# IO_Top_Board.net
KiCad netlist of a schematic drawn in EAGLE
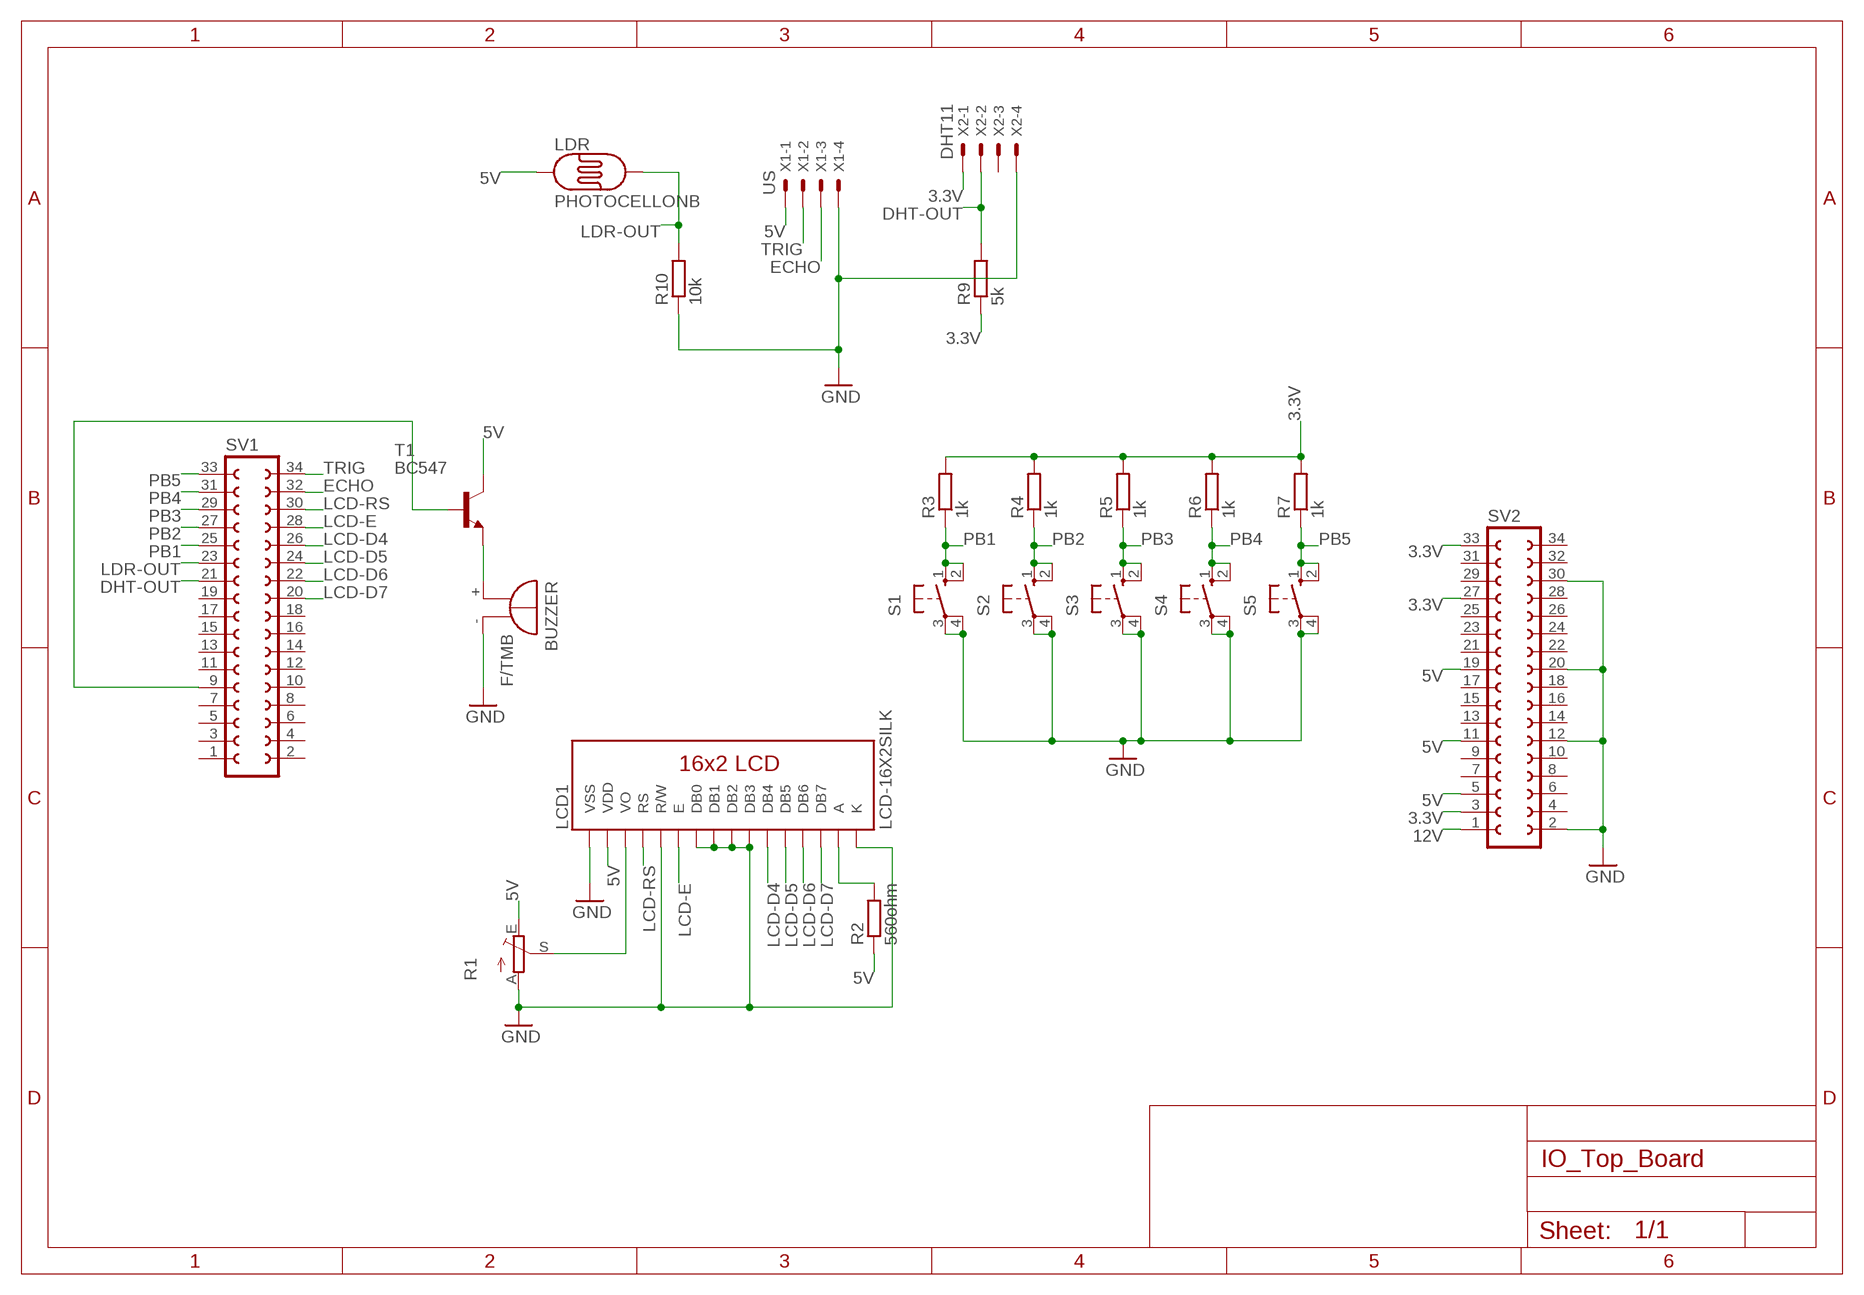
[diagram p0: schematic, sheet 1]

(export (version "E")
  (design (tool "Eeschema 10.0.6"))
  (components
    (comp (ref "BUZZER")
      (value "F/TMB")
      (footprint "eagle-import:F_TMB")
      (libsource (lib "eagle-import") (part "F/TMB"))
    )
    (comp (ref "LCD1")
      (value "LCD-16X2SILK")
      (footprint "eagle-import:LCD-16X2")
      (libsource (lib "eagle-import") (part "LCD-16X2SILK"))
    )
    (comp (ref "LDR")
      (value "PHOTOCELLONB")
      (footprint "eagle-import:ON_BOARD")
      (libsource (lib "eagle-import") (part "PHOTOCELLONB"))
    )
    (comp (ref "R1")
      (value "TRIM_EU-CA6V")
      (footprint "eagle-import:CA6V")
      (libsource (lib "eagle-import") (part "TRIM_EU-CA6V"))
    )
    (comp (ref "R2")
      (value "560ohm")
      (footprint "eagle-import:M0805")
      (libsource (lib "eagle-import") (part "R-EU_M0805"))
    )
    (comp (ref "R3")
      (value "1k")
      (footprint "eagle-import:M0805")
      (libsource (lib "eagle-import") (part "R-EU_M0805"))
    )
    (comp (ref "R4")
      (value "1k")
      (footprint "eagle-import:M0805")
      (libsource (lib "eagle-import") (part "R-EU_M0805"))
    )
    (comp (ref "R5")
      (value "1k")
      (footprint "eagle-import:M0805")
      (libsource (lib "eagle-import") (part "R-EU_M0805"))
    )
    (comp (ref "R6")
      (value "1k")
      (footprint "eagle-import:M0805")
      (libsource (lib "eagle-import") (part "R-EU_M0805"))
    )
    (comp (ref "R7")
      (value "1k")
      (footprint "eagle-import:M0805")
      (libsource (lib "eagle-import") (part "R-EU_M0805"))
    )
    (comp (ref "R9")
      (value "5k")
      (footprint "eagle-import:M0805")
      (libsource (lib "eagle-import") (part "R-EU_M0805"))
    )
    (comp (ref "R10")
      (value "10k")
      (footprint "eagle-import:M0805")
      (libsource (lib "eagle-import") (part "R-EU_M0805"))
    )
    (comp (ref "S1")
      (value "10-XX")
      (footprint "eagle-import:B3F-10XX")
      (fields (field (name "MPN") "B3F-1000"))
      (libsource (lib "eagle-import") (part "10-XX"))
    )
    (comp (ref "S2")
      (value "10-XX")
      (footprint "eagle-import:B3F-10XX")
      (fields (field (name "MPN") "B3F-1000"))
      (libsource (lib "eagle-import") (part "10-XX"))
    )
    (comp (ref "S3")
      (value "10-XX")
      (footprint "eagle-import:B3F-10XX")
      (fields (field (name "MPN") "B3F-1000"))
      (libsource (lib "eagle-import") (part "10-XX"))
    )
    (comp (ref "S4")
      (value "10-XX")
      (footprint "eagle-import:B3F-10XX")
      (fields (field (name "MPN") "B3F-1000"))
      (libsource (lib "eagle-import") (part "10-XX"))
    )
    (comp (ref "S5")
      (value "10-XX")
      (footprint "eagle-import:B3F-10XX")
      (fields (field (name "MPN") "B3F-1000"))
      (libsource (lib "eagle-import") (part "10-XX"))
    )
    (comp (ref "SV1")
      (value "FE17-2W")
      (footprint "eagle-import:FE17-2W")
      (libsource (lib "eagle-import") (part "FE17-2W"))
    )
    (comp (ref "SV2")
      (value "FE17-2W")
      (footprint "eagle-import:FE17-2W")
      (libsource (lib "eagle-import") (part "FE17-2W"))
    )
    (comp (ref "T1")
      (value "BC547")
      (footprint "eagle-import:TO92")
      (libsource (lib "eagle-import") (part "BC547"))
    )
    (comp (ref "X1")
      (value "US")
      (footprint "eagle-import:22-23-2041")
      (fields (field (name "MF") "MOLEX") (field (name "MPN") "22-23-2041"))
      (libsource (lib "eagle-import") (part "22-23-2041"))
    )
    (comp (ref "X2")
      (value "DHT11")
      (footprint "eagle-import:22-23-2041")
      (fields (field (name "MF") "MOLEX") (field (name "MPN") "22-23-2041"))
      (libsource (lib "eagle-import") (part "22-23-2041"))
    )
  )
  (nets
    (net (code "1") (name "/3.3V") (class "Default")
      (node (ref "R3") (pin "2") (pinfunction "2_2") (pintype "passive"))
      (node (ref "R4") (pin "2") (pinfunction "2_2") (pintype "passive"))
      (node (ref "R5") (pin "2") (pinfunction "2_2") (pintype "passive"))
      (node (ref "R6") (pin "2") (pinfunction "2_2") (pintype "passive"))
      (node (ref "R7") (pin "2") (pinfunction "2_2") (pintype "passive"))
      (node (ref "R9") (pin "1") (pinfunction "1_1") (pintype "passive"))
      (node (ref "SV2") (pin "27") (pinfunction "27_27") (pintype "passive"))
      (node (ref "SV2") (pin "3") (pinfunction "3_3") (pintype "passive"))
      (node (ref "SV2") (pin "33") (pinfunction "33_33") (pintype "passive"))
      (node (ref "X2") (pin "1") (pinfunction "S_1") (pintype "passive"))
    )
    (net (code "2") (name "/5V") (class "Default")
      (node (ref "LCD1") (pin "2") (pinfunction "VDD_2") (pintype "power_in"))
      (node (ref "LDR") (pin "1") (pinfunction "P$1_1") (pintype "bidirectional"))
      (node (ref "R1") (pin "E") (pinfunction "E_E") (pintype "passive"))
      (node (ref "R2") (pin "1") (pinfunction "1_1") (pintype "passive"))
      (node (ref "SV2") (pin "11") (pinfunction "11_11") (pintype "passive"))
      (node (ref "SV2") (pin "19") (pinfunction "19_19") (pintype "passive"))
      (node (ref "SV2") (pin "5") (pinfunction "5_5") (pintype "passive"))
      (node (ref "T1") (pin "3") (pinfunction "C_3") (pintype "passive"))
      (node (ref "X1") (pin "1") (pinfunction "S_1") (pintype "passive"))
    )
    (net (code "3") (name "/12V") (class "Default")
      (node (ref "SV2") (pin "1") (pinfunction "1_1") (pintype "passive"))
    )
    (net (code "4") (name "/DHT-OUT") (class "Default")
      (node (ref "R9") (pin "2") (pinfunction "2_2") (pintype "passive"))
      (node (ref "SV1") (pin "21") (pinfunction "21_21") (pintype "passive"))
      (node (ref "X2") (pin "2") (pinfunction "S_2") (pintype "passive"))
    )
    (net (code "5") (name "/ECHO") (class "Default")
      (node (ref "SV1") (pin "32") (pinfunction "32_32") (pintype "passive"))
      (node (ref "X1") (pin "3") (pinfunction "S_3") (pintype "passive"))
    )
    (net (code "6") (name "/LCD-D4") (class "Default")
      (node (ref "LCD1") (pin "11") (pinfunction "DB4_11") (pintype "bidirectional"))
      (node (ref "SV1") (pin "26") (pinfunction "26_26") (pintype "passive"))
    )
    (net (code "7") (name "/LCD-D5") (class "Default")
      (node (ref "LCD1") (pin "12") (pinfunction "DB5_12") (pintype "bidirectional"))
      (node (ref "SV1") (pin "24") (pinfunction "24_24") (pintype "passive"))
    )
    (net (code "8") (name "/LCD-D6") (class "Default")
      (node (ref "LCD1") (pin "13") (pinfunction "DB6_13") (pintype "bidirectional"))
      (node (ref "SV1") (pin "22") (pinfunction "22_22") (pintype "passive"))
    )
    (net (code "9") (name "/LCD-D7") (class "Default")
      (node (ref "LCD1") (pin "14") (pinfunction "DB7_14") (pintype "bidirectional"))
      (node (ref "SV1") (pin "20") (pinfunction "20_20") (pintype "passive"))
    )
    (net (code "10") (name "/LCD-E") (class "Default")
      (node (ref "LCD1") (pin "6") (pinfunction "E_6") (pintype "input"))
      (node (ref "SV1") (pin "28") (pinfunction "28_28") (pintype "passive"))
    )
    (net (code "11") (name "/LCD-RS") (class "Default")
      (node (ref "LCD1") (pin "4") (pinfunction "RS_4") (pintype "input"))
      (node (ref "SV1") (pin "30") (pinfunction "30_30") (pintype "passive"))
    )
    (net (code "12") (name "/LDR-OUT") (class "Default")
      (node (ref "LDR") (pin "2") (pinfunction "P$2_2") (pintype "bidirectional"))
      (node (ref "R10") (pin "2") (pinfunction "2_2") (pintype "passive"))
      (node (ref "SV1") (pin "23") (pinfunction "23_23") (pintype "passive"))
    )
    (net (code "13") (name "/PB1") (class "Default")
      (node (ref "R3") (pin "1") (pinfunction "1_1") (pintype "passive"))
      (node (ref "S1") (pin "1") (pinfunction "S_1") (pintype "passive"))
      (node (ref "S1") (pin "2") (pinfunction "S1_2") (pintype "passive"))
      (node (ref "SV1") (pin "25") (pinfunction "25_25") (pintype "passive"))
    )
    (net (code "14") (name "/PB2") (class "Default")
      (node (ref "R4") (pin "1") (pinfunction "1_1") (pintype "passive"))
      (node (ref "S2") (pin "1") (pinfunction "S_1") (pintype "passive"))
      (node (ref "S2") (pin "2") (pinfunction "S1_2") (pintype "passive"))
      (node (ref "SV1") (pin "27") (pinfunction "27_27") (pintype "passive"))
    )
    (net (code "15") (name "/PB3") (class "Default")
      (node (ref "R5") (pin "1") (pinfunction "1_1") (pintype "passive"))
      (node (ref "S3") (pin "1") (pinfunction "S_1") (pintype "passive"))
      (node (ref "S3") (pin "2") (pinfunction "S1_2") (pintype "passive"))
      (node (ref "SV1") (pin "29") (pinfunction "29_29") (pintype "passive"))
    )
    (net (code "16") (name "/PB4") (class "Default")
      (node (ref "R6") (pin "1") (pinfunction "1_1") (pintype "passive"))
      (node (ref "S4") (pin "1") (pinfunction "S_1") (pintype "passive"))
      (node (ref "S4") (pin "2") (pinfunction "S1_2") (pintype "passive"))
      (node (ref "SV1") (pin "31") (pinfunction "31_31") (pintype "passive"))
    )
    (net (code "17") (name "/PB5") (class "Default")
      (node (ref "R7") (pin "1") (pinfunction "1_1") (pintype "passive"))
      (node (ref "S5") (pin "1") (pinfunction "S_1") (pintype "passive"))
      (node (ref "S5") (pin "2") (pinfunction "S1_2") (pintype "passive"))
      (node (ref "SV1") (pin "33") (pinfunction "33_33") (pintype "passive"))
    )
    (net (code "18") (name "/TRIG") (class "Default")
      (node (ref "SV1") (pin "34") (pinfunction "34_34") (pintype "passive"))
      (node (ref "X1") (pin "2") (pinfunction "S_2") (pintype "passive"))
    )
    (net (code "19") (name "GND") (class "Default")
      (node (ref "BUZZER") (pin "-") (pinfunction "-_-") (pintype "passive"))
      (node (ref "LCD1") (pin "1") (pinfunction "VSS_1") (pintype "power_in"))
      (node (ref "LCD1") (pin "10") (pinfunction "DB3_10") (pintype "bidirectional"))
      (node (ref "LCD1") (pin "16") (pinfunction "K_16") (pintype "power_in"))
      (node (ref "LCD1") (pin "5") (pinfunction "R/W_5") (pintype "input"))
      (node (ref "LCD1") (pin "7") (pinfunction "DB0_7") (pintype "bidirectional"))
      (node (ref "LCD1") (pin "8") (pinfunction "DB1_8") (pintype "bidirectional"))
      (node (ref "LCD1") (pin "9") (pinfunction "DB2_9") (pintype "bidirectional"))
      (node (ref "R1") (pin "A") (pinfunction "A_A") (pintype "passive"))
      (node (ref "R10") (pin "1") (pinfunction "1_1") (pintype "passive"))
      (node (ref "S1") (pin "3") (pinfunction "P_3") (pintype "passive"))
      (node (ref "S1") (pin "4") (pinfunction "P1_4") (pintype "passive"))
      (node (ref "S2") (pin "3") (pinfunction "P_3") (pintype "passive"))
      (node (ref "S2") (pin "4") (pinfunction "P1_4") (pintype "passive"))
      (node (ref "S3") (pin "3") (pinfunction "P_3") (pintype "passive"))
      (node (ref "S3") (pin "4") (pinfunction "P1_4") (pintype "passive"))
      (node (ref "S4") (pin "3") (pinfunction "P_3") (pintype "passive"))
      (node (ref "S4") (pin "4") (pinfunction "P1_4") (pintype "passive"))
      (node (ref "S5") (pin "3") (pinfunction "P_3") (pintype "passive"))
      (node (ref "S5") (pin "4") (pinfunction "P1_4") (pintype "passive"))
      (node (ref "SV2") (pin "12") (pinfunction "12_12") (pintype "passive"))
      (node (ref "SV2") (pin "2") (pinfunction "2_2") (pintype "passive"))
      (node (ref "SV2") (pin "20") (pinfunction "20_20") (pintype "passive"))
      (node (ref "SV2") (pin "30") (pinfunction "30_30") (pintype "passive"))
      (node (ref "X1") (pin "4") (pinfunction "S_4") (pintype "passive"))
      (node (ref "X2") (pin "4") (pinfunction "S_4") (pintype "passive"))
    )
    (net (code "20") (name "Net-(LCD1-A)") (class "Default")
      (node (ref "LCD1") (pin "15") (pinfunction "A_15") (pintype "power_in"))
      (node (ref "R2") (pin "2") (pinfunction "2_2") (pintype "passive"))
    )
    (net (code "21") (name "Net-(LCD1-VO)") (class "Default")
      (node (ref "LCD1") (pin "3") (pinfunction "VO_3") (pintype "bidirectional"))
      (node (ref "R1") (pin "S") (pinfunction "S_S") (pintype "passive"))
    )
    (net (code "22") (name "Net-(T1-B)") (class "Default")
      (node (ref "SV1") (pin "9") (pinfunction "9_9") (pintype "passive"))
      (node (ref "T1") (pin "2") (pinfunction "B_2") (pintype "passive"))
    )
    (net (code "23") (name "Net-(T1-E)") (class "Default")
      (node (ref "BUZZER") (pin "+") (pinfunction "+_+") (pintype "passive"))
      (node (ref "T1") (pin "1") (pinfunction "E_1") (pintype "passive"))
    )
    (net (code "24") (name "unconnected-(SV1-Pad1)") (class "Default")
      (node (ref "SV1") (pin "1") (pinfunction "1_1") (pintype "passive"))
    )
    (net (code "25") (name "unconnected-(SV1-Pad2)") (class "Default")
      (node (ref "SV1") (pin "2") (pinfunction "2_2") (pintype "passive"))
    )
    (net (code "26") (name "unconnected-(SV1-Pad3)") (class "Default")
      (node (ref "SV1") (pin "3") (pinfunction "3_3") (pintype "passive"))
    )
    (net (code "27") (name "unconnected-(SV1-Pad4)") (class "Default")
      (node (ref "SV1") (pin "4") (pinfunction "4_4") (pintype "passive"))
    )
    (net (code "28") (name "unconnected-(SV1-Pad5)") (class "Default")
      (node (ref "SV1") (pin "5") (pinfunction "5_5") (pintype "passive"))
    )
    (net (code "29") (name "unconnected-(SV1-Pad6)") (class "Default")
      (node (ref "SV1") (pin "6") (pinfunction "6_6") (pintype "passive"))
    )
    (net (code "30") (name "unconnected-(SV1-Pad7)") (class "Default")
      (node (ref "SV1") (pin "7") (pinfunction "7_7") (pintype "passive"))
    )
    (net (code "31") (name "unconnected-(SV1-Pad8)") (class "Default")
      (node (ref "SV1") (pin "8") (pinfunction "8_8") (pintype "passive"))
    )
    (net (code "32") (name "unconnected-(SV1-Pad10)") (class "Default")
      (node (ref "SV1") (pin "10") (pinfunction "10_10") (pintype "passive"))
    )
    (net (code "33") (name "unconnected-(SV1-Pad11)") (class "Default")
      (node (ref "SV1") (pin "11") (pinfunction "11_11") (pintype "passive"))
    )
    (net (code "34") (name "unconnected-(SV1-Pad12)") (class "Default")
      (node (ref "SV1") (pin "12") (pinfunction "12_12") (pintype "passive"))
    )
    (net (code "35") (name "unconnected-(SV1-Pad13)") (class "Default")
      (node (ref "SV1") (pin "13") (pinfunction "13_13") (pintype "passive"))
    )
    (net (code "36") (name "unconnected-(SV1-Pad14)") (class "Default")
      (node (ref "SV1") (pin "14") (pinfunction "14_14") (pintype "passive"))
    )
    (net (code "37") (name "unconnected-(SV1-Pad15)") (class "Default")
      (node (ref "SV1") (pin "15") (pinfunction "15_15") (pintype "passive"))
    )
    (net (code "38") (name "unconnected-(SV1-Pad16)") (class "Default")
      (node (ref "SV1") (pin "16") (pinfunction "16_16") (pintype "passive"))
    )
    (net (code "39") (name "unconnected-(SV1-Pad17)") (class "Default")
      (node (ref "SV1") (pin "17") (pinfunction "17_17") (pintype "passive"))
    )
    (net (code "40") (name "unconnected-(SV1-Pad18)") (class "Default")
      (node (ref "SV1") (pin "18") (pinfunction "18_18") (pintype "passive"))
    )
    (net (code "41") (name "unconnected-(SV1-Pad19)") (class "Default")
      (node (ref "SV1") (pin "19") (pinfunction "19_19") (pintype "passive"))
    )
    (net (code "42") (name "unconnected-(SV2-Pad4)") (class "Default")
      (node (ref "SV2") (pin "4") (pinfunction "4_4") (pintype "passive"))
    )
    (net (code "43") (name "unconnected-(SV2-Pad6)") (class "Default")
      (node (ref "SV2") (pin "6") (pinfunction "6_6") (pintype "passive"))
    )
    (net (code "44") (name "unconnected-(SV2-Pad7)") (class "Default")
      (node (ref "SV2") (pin "7") (pinfunction "7_7") (pintype "passive"))
    )
    (net (code "45") (name "unconnected-(SV2-Pad8)") (class "Default")
      (node (ref "SV2") (pin "8") (pinfunction "8_8") (pintype "passive"))
    )
    (net (code "46") (name "unconnected-(SV2-Pad9)") (class "Default")
      (node (ref "SV2") (pin "9") (pinfunction "9_9") (pintype "passive"))
    )
    (net (code "47") (name "unconnected-(SV2-Pad10)") (class "Default")
      (node (ref "SV2") (pin "10") (pinfunction "10_10") (pintype "passive"))
    )
    (net (code "48") (name "unconnected-(SV2-Pad13)") (class "Default")
      (node (ref "SV2") (pin "13") (pinfunction "13_13") (pintype "passive"))
    )
    (net (code "49") (name "unconnected-(SV2-Pad14)") (class "Default")
      (node (ref "SV2") (pin "14") (pinfunction "14_14") (pintype "passive"))
    )
    (net (code "50") (name "unconnected-(SV2-Pad15)") (class "Default")
      (node (ref "SV2") (pin "15") (pinfunction "15_15") (pintype "passive"))
    )
    (net (code "51") (name "unconnected-(SV2-Pad16)") (class "Default")
      (node (ref "SV2") (pin "16") (pinfunction "16_16") (pintype "passive"))
    )
    (net (code "52") (name "unconnected-(SV2-Pad17)") (class "Default")
      (node (ref "SV2") (pin "17") (pinfunction "17_17") (pintype "passive"))
    )
    (net (code "53") (name "unconnected-(SV2-Pad18)") (class "Default")
      (node (ref "SV2") (pin "18") (pinfunction "18_18") (pintype "passive"))
    )
    (net (code "54") (name "unconnected-(SV2-Pad21)") (class "Default")
      (node (ref "SV2") (pin "21") (pinfunction "21_21") (pintype "passive"))
    )
    (net (code "55") (name "unconnected-(SV2-Pad22)") (class "Default")
      (node (ref "SV2") (pin "22") (pinfunction "22_22") (pintype "passive"))
    )
    (net (code "56") (name "unconnected-(SV2-Pad23)") (class "Default")
      (node (ref "SV2") (pin "23") (pinfunction "23_23") (pintype "passive"))
    )
    (net (code "57") (name "unconnected-(SV2-Pad24)") (class "Default")
      (node (ref "SV2") (pin "24") (pinfunction "24_24") (pintype "passive"))
    )
    (net (code "58") (name "unconnected-(SV2-Pad25)") (class "Default")
      (node (ref "SV2") (pin "25") (pinfunction "25_25") (pintype "passive"))
    )
    (net (code "59") (name "unconnected-(SV2-Pad26)") (class "Default")
      (node (ref "SV2") (pin "26") (pinfunction "26_26") (pintype "passive"))
    )
    (net (code "60") (name "unconnected-(SV2-Pad28)") (class "Default")
      (node (ref "SV2") (pin "28") (pinfunction "28_28") (pintype "passive"))
    )
    (net (code "61") (name "unconnected-(SV2-Pad29)") (class "Default")
      (node (ref "SV2") (pin "29") (pinfunction "29_29") (pintype "passive"))
    )
    (net (code "62") (name "unconnected-(SV2-Pad31)") (class "Default")
      (node (ref "SV2") (pin "31") (pinfunction "31_31") (pintype "passive"))
    )
    (net (code "63") (name "unconnected-(SV2-Pad32)") (class "Default")
      (node (ref "SV2") (pin "32") (pinfunction "32_32") (pintype "passive"))
    )
    (net (code "64") (name "unconnected-(SV2-Pad34)") (class "Default")
      (node (ref "SV2") (pin "34") (pinfunction "34_34") (pintype "passive"))
    )
    (net (code "65") (name "unconnected-(X2C-S-Pad3)") (class "Default")
      (node (ref "X2") (pin "3") (pinfunction "S_3") (pintype "passive"))
    )
  )
)
